# Sheet3.net
KiCad netlist of a schematic drawn in Altium Designer
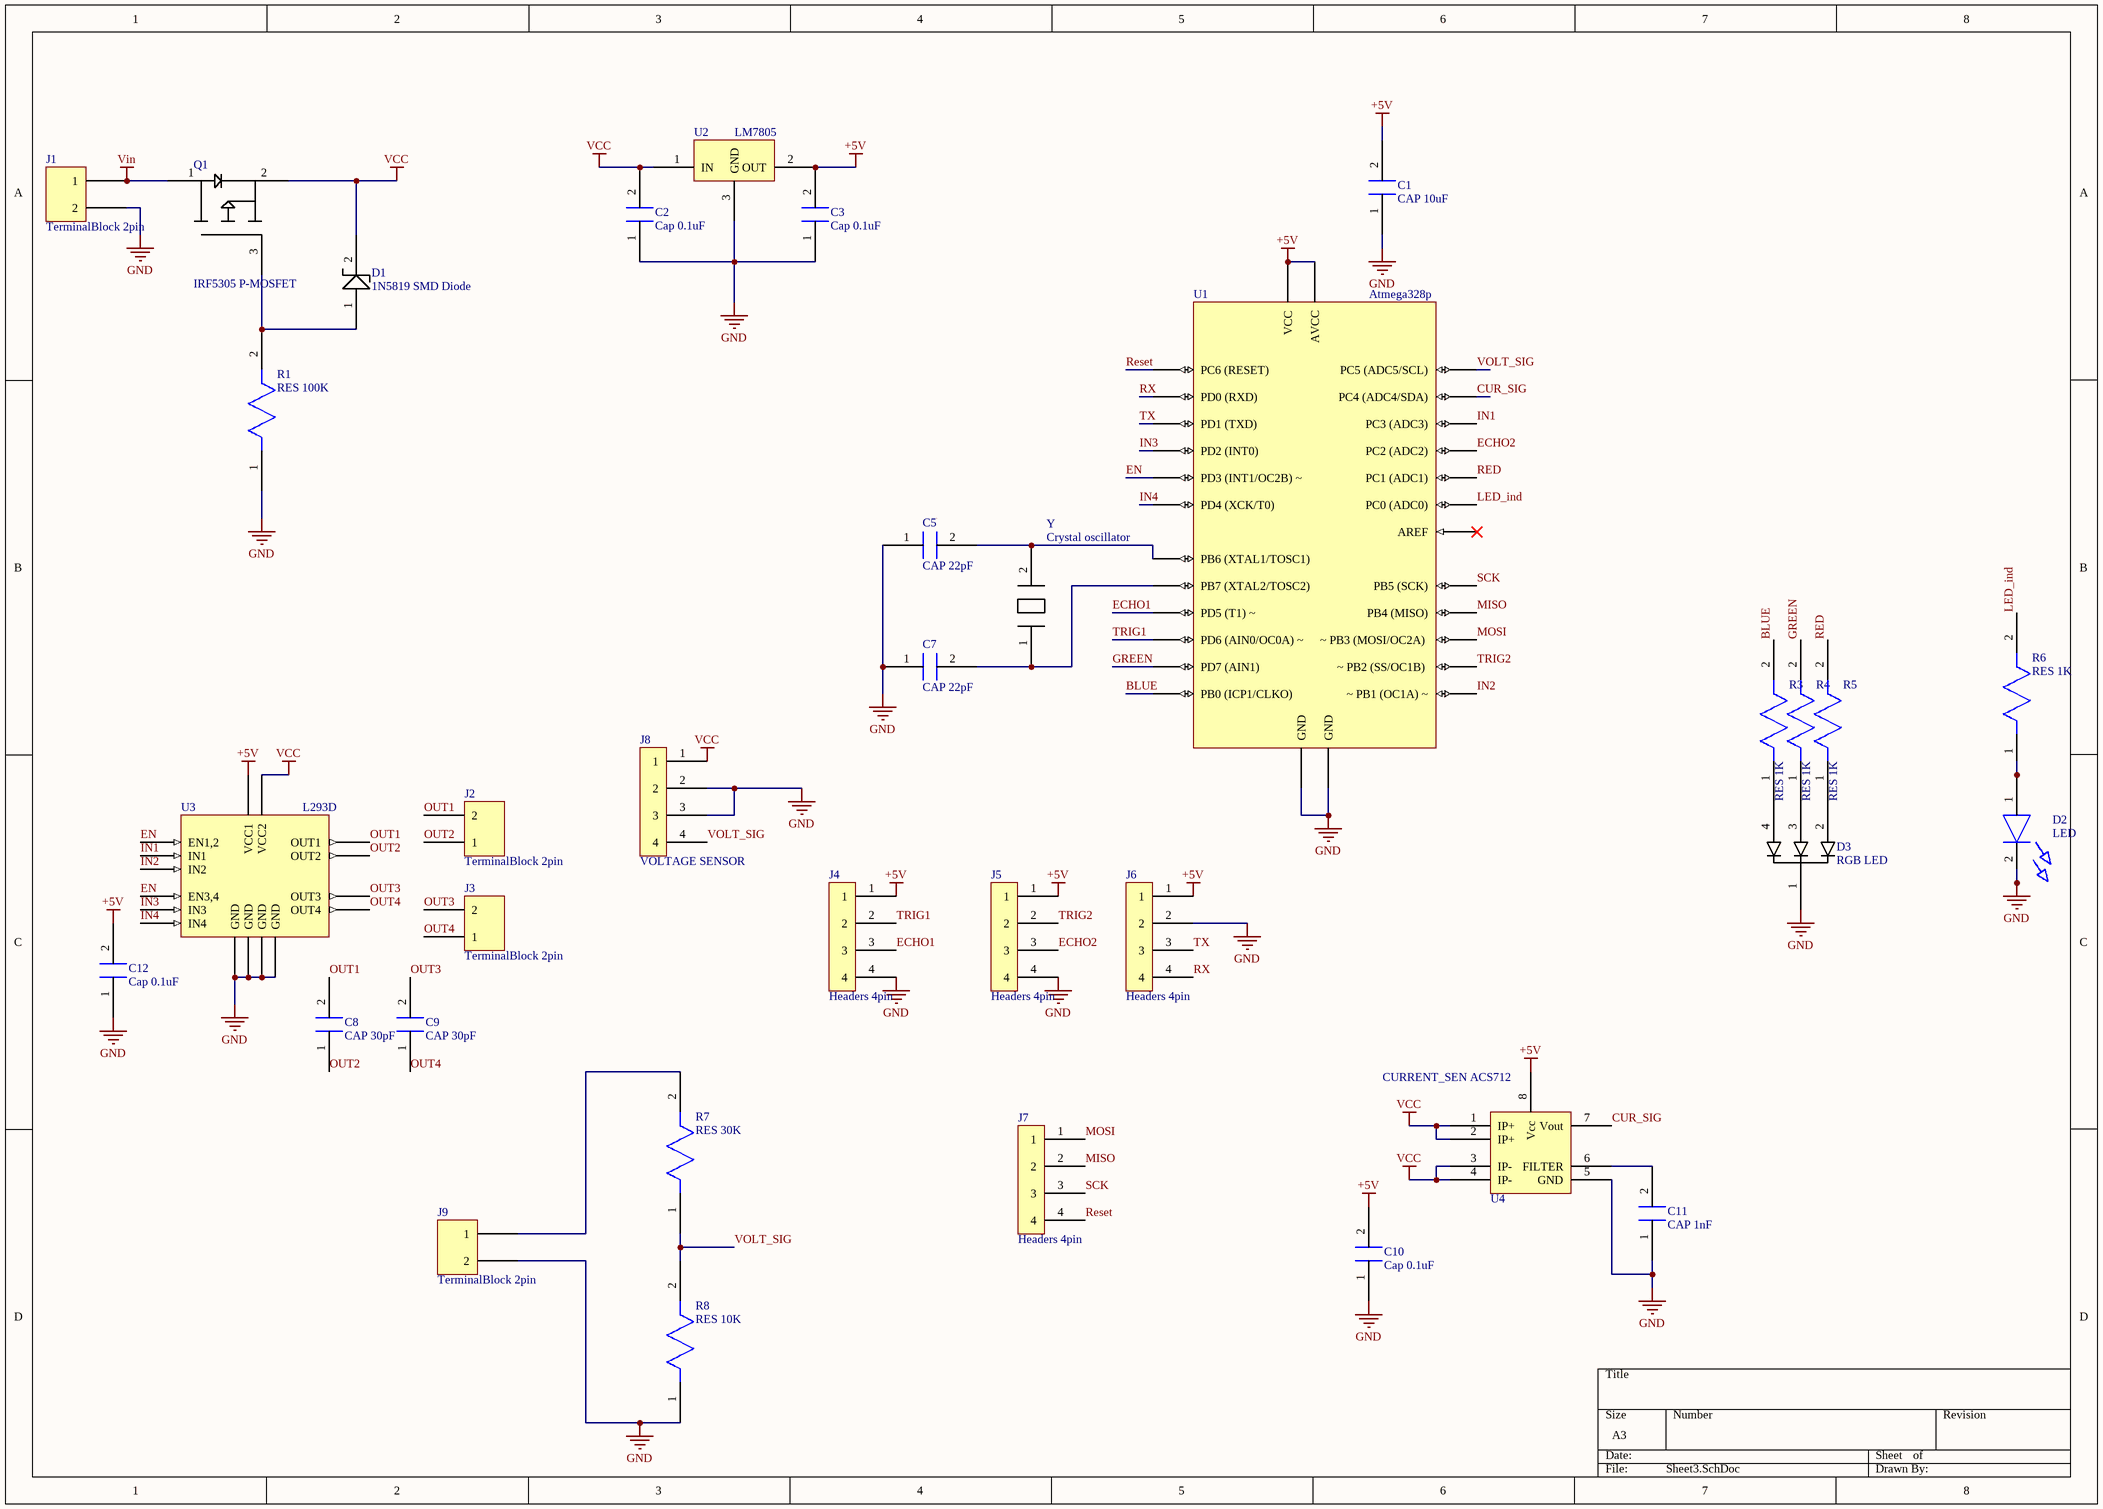
[diagram p0: Sheet3.SchDoc]

(export (version "E")
  (design (tool "Eeschema 10.0.6"))
  (components
    (comp (ref "C1") (value "CAP 10uF") (footprint "Cap 10uF") (libsource (lib "Schlib1") (part "CAP 10uF")))
    (comp (ref "C2")
      (value "Cap 0.1uF")
      (footprint "CAP 0.1uF")
      (libsource (lib "Schlib1") (part "Cap 0.1uF"))
    )
    (comp (ref "C3")
      (value "Cap 0.1uF")
      (footprint "CAP 0.1uF")
      (libsource (lib "Schlib1") (part "Cap 0.1uF"))
    )
    (comp (ref "C5") (value "CAP 22pF") (footprint "Cap 22pF") (libsource (lib "Schlib1") (part "CAP 22pF")))
    (comp (ref "C7") (value "CAP 22pF") (footprint "Cap 22pF") (libsource (lib "Schlib1") (part "CAP 22pF")))
    (comp (ref "C8") (value "CAP 30pF") (footprint "CAP 30pF") (libsource (lib "Schlib1") (part "CAP 30pF")))
    (comp (ref "C9") (value "CAP 30pF") (footprint "CAP 30pF") (libsource (lib "Schlib1") (part "CAP 30pF")))
    (comp (ref "C10")
      (value "Cap 0.1uF")
      (footprint "CAP 0.1uF")
      (libsource (lib "Schlib1") (part "Cap 0.1uF"))
    )
    (comp (ref "C11") (value "CAP 1nF") (footprint "CAP 1nF") (libsource (lib "Schlib1") (part "CAP 1nF")))
    (comp (ref "C12")
      (value "Cap 0.1uF")
      (footprint "CAP 0.1uF")
      (libsource (lib "Schlib1") (part "Cap 0.1uF"))
    )
    (comp (ref "D1")
      (value "1N5819 SMD Diode")
      (footprint "1N5819 SMD Diode")
      (libsource (lib "Schlib1") (part "1N5819 SMD Diode"))
    )
    (comp (ref "D2") (value "LED") (footprint "LED") (libsource (lib "Schlib1") (part "LED")))
    (comp (ref "D3") (value "RGB LED") (footprint "RGB LED") (libsource (lib "Schlib1") (part "RGB LED")))
    (comp (ref "J1")
      (value "TerminalBlock 2pin")
      (footprint "Terminal Block 2pin")
      (libsource (lib "Schlib1") (part "TerminalBlock 2pin"))
    )
    (comp (ref "J2")
      (value "TerminalBlock 2pin")
      (footprint "Terminal Block 2pin")
      (libsource (lib "") (part "TerminalBlock 2pin_1"))
    )
    (comp (ref "J3")
      (value "TerminalBlock 2pin")
      (footprint "Terminal Block 2pin")
      (libsource (lib "") (part "TerminalBlock 2pin_1"))
    )
    (comp (ref "J4")
      (value "Headers 4pin")
      (footprint "Header 4pin")
      (libsource (lib "Schlib1") (part "Headers 4pin"))
    )
    (comp (ref "J5")
      (value "Headers 4pin")
      (footprint "Header 4pin")
      (libsource (lib "Schlib1") (part "Headers 4pin"))
    )
    (comp (ref "J6")
      (value "Headers 4pin")
      (footprint "Header 4pin")
      (libsource (lib "Schlib1") (part "Headers 4pin"))
    )
    (comp (ref "J7")
      (value "Headers 4pin")
      (footprint "Header 4pin")
      (libsource (lib "Schlib1") (part "Headers 4pin"))
    )
    (comp (ref "J8")
      (value "VOLTAGE SENSOR")
      (footprint "Header 4pin")
      (libsource (lib "Schlib1") (part "Headers 4pin"))
    )
    (comp (ref "J9")
      (value "TerminalBlock 2pin")
      (footprint "Terminal Block 2pin")
      (libsource (lib "Schlib1") (part "TerminalBlock 2pin"))
    )
    (comp (ref "Q1")
      (value "IRF5305 P-MOSFET")
      (footprint "IRF5305")
      (libsource (lib "Schlib1") (part "IRF5305 P-MOSFET"))
    )
    (comp (ref "R1") (value "RES 100K") (footprint "Res100K") (libsource (lib "Schlib1") (part "RES 100K")))
    (comp (ref "R3") (value "RES 1K") (footprint "Res 1K") (libsource (lib "Schlib1") (part "RES 1K")))
    (comp (ref "R4") (value "RES 1K") (footprint "Res 1K") (libsource (lib "Schlib1") (part "RES 1K")))
    (comp (ref "R5") (value "RES 1K") (footprint "Res 1K") (libsource (lib "Schlib1") (part "RES 1K")))
    (comp (ref "R6") (value "RES 1K") (footprint "Res 1K") (libsource (lib "Schlib1") (part "RES 1K")))
    (comp (ref "R7") (value "RES 30K") (footprint "Res100K") (libsource (lib "Schlib1") (part "RES 100K")))
    (comp (ref "R8") (value "RES 10K") (footprint "Res10K") (libsource (lib "Schlib1") (part "RES 10K")))
    (comp (ref "U1")
      (value "Atmega328p")
      (footprint "ATMega 328 P-PU - duplicate")
      (libsource (lib "Schlib1") (part "Atmega328p"))
    )
    (comp (ref "U2") (value "LM7805") (footprint "LM7805") (libsource (lib "Schlib1") (part "LM7805")))
    (comp (ref "U3") (value "L293D") (footprint "L293D") (libsource (lib "Schlib1") (part "L293D")))
    (comp (ref "U4")
      (value "CURRENT_SEN ACS712")
      (footprint "Cuurent_sens")
      (libsource (lib "Schlib1") (part "CURRENT_MOD ACS712"))
    )
    (comp (ref "Y")
      (value "Crystal oscillator")
      (footprint "Crrystal 16MHZ")
      (libsource (lib "Schlib1") (part "Crystal oscillator"))
    )
  )
  (nets
    (net (code "1") (name "+5V") (class "Default")
      (node (ref "C1") (pin "2") (pinfunction "2_2") (pintype "passive"))
      (node (ref "C10") (pin "2") (pinfunction "2_2") (pintype "passive"))
      (node (ref "C12") (pin "2") (pinfunction "2_2") (pintype "passive"))
      (node (ref "C3") (pin "2") (pinfunction "2_2") (pintype "passive"))
      (node (ref "J4") (pin "1") (pinfunction "1_1") (pintype "passive"))
      (node (ref "J5") (pin "1") (pinfunction "1_1") (pintype "passive"))
      (node (ref "J6") (pin "1") (pinfunction "1_1") (pintype "passive"))
      (node (ref "U1") (pin "20") (pinfunction "AVCC_20") (pintype "passive"))
      (node (ref "U1") (pin "7") (pinfunction "VCC_7") (pintype "passive"))
      (node (ref "U2") (pin "2") (pinfunction "OUT_2") (pintype "passive"))
      (node (ref "U3") (pin "16") (pinfunction "VCC1_16") (pintype "power_in"))
      (node (ref "U4") (pin "8") (pinfunction "Vcc_8") (pintype "passive"))
    )
    (net (code "3") (name "/BLUE") (class "Default")
      (node (ref "R3") (pin "2") (pinfunction "4_2") (pintype "passive"))
      (node (ref "U1") (pin "14") (pinfunction "PB0_(ICP1/CLKO)_14") (pintype "bidirectional"))
    )
    (net (code "4") (name "/CUR_SIG") (class "Default")
      (node (ref "U1") (pin "27") (pinfunction "PC4_(ADC4/SDA)_27") (pintype "bidirectional"))
      (node (ref "U4") (pin "7") (pinfunction "Vout_7") (pintype "passive"))
    )
    (net (code "5") (name "/ECHO1") (class "Default")
      (node (ref "J4") (pin "3") (pinfunction "3_3") (pintype "passive"))
      (node (ref "U1") (pin "11") (pinfunction "PD5_(T1)_~_11") (pintype "bidirectional"))
    )
    (net (code "6") (name "/ECHO2") (class "Default")
      (node (ref "J5") (pin "3") (pinfunction "3_3") (pintype "passive"))
      (node (ref "U1") (pin "25") (pinfunction "PC2_(ADC2)_25") (pintype "bidirectional"))
    )
    (net (code "7") (name "/EN") (class "Default")
      (node (ref "U1") (pin "5") (pinfunction "PD3_(INT1/OC2B)_~_5") (pintype "bidirectional"))
      (node (ref "U3") (pin "1") (pinfunction "EN1,2_1") (pintype "input"))
      (node (ref "U3") (pin "9") (pinfunction "EN3,4_9") (pintype "input"))
    )
    (net (code "8") (name "/GREEN") (class "Default")
      (node (ref "R4") (pin "2") (pinfunction "4_2") (pintype "passive"))
      (node (ref "U1") (pin "13") (pinfunction "PD7_(AIN1)_13") (pintype "bidirectional"))
    )
    (net (code "9") (name "/IN1") (class "Default")
      (node (ref "U1") (pin "26") (pinfunction "PC3_(ADC3)_26") (pintype "bidirectional"))
      (node (ref "U3") (pin "2") (pinfunction "IN1_2") (pintype "input"))
    )
    (net (code "10") (name "/IN2") (class "Default")
      (node (ref "U1") (pin "15") (pinfunction "~_PB1_(OC1A)_~_15") (pintype "bidirectional"))
      (node (ref "U3") (pin "7") (pinfunction "IN2_7") (pintype "input"))
    )
    (net (code "11") (name "/IN3") (class "Default")
      (node (ref "U1") (pin "4") (pinfunction "PD2_(INT0)_4") (pintype "bidirectional"))
      (node (ref "U3") (pin "10") (pinfunction "IN3_10") (pintype "input"))
    )
    (net (code "12") (name "/IN4") (class "Default")
      (node (ref "U1") (pin "6") (pinfunction "PD4_(XCK/T0)_6") (pintype "bidirectional"))
      (node (ref "U3") (pin "15") (pinfunction "IN4_15") (pintype "input"))
    )
    (net (code "13") (name "/LED_ind") (class "Default")
      (node (ref "R6") (pin "2") (pinfunction "4_2") (pintype "passive"))
      (node (ref "U1") (pin "23") (pinfunction "PC0_(ADC0)_23") (pintype "bidirectional"))
    )
    (net (code "14") (name "/MISO") (class "Default")
      (node (ref "J7") (pin "2") (pinfunction "2_2") (pintype "passive"))
      (node (ref "U1") (pin "18") (pinfunction "PB4_(MISO)_18") (pintype "bidirectional"))
    )
    (net (code "15") (name "/MOSI") (class "Default")
      (node (ref "J7") (pin "1") (pinfunction "1_1") (pintype "passive"))
      (node (ref "U1") (pin "17") (pinfunction "~_PB3_(MOSI/OC2A)_17") (pintype "bidirectional"))
    )
    (net (code "16") (name "/OUT1") (class "Default")
      (node (ref "C8") (pin "2") (pinfunction "2_2") (pintype "passive"))
      (node (ref "J2") (pin "2") (pinfunction "2_2") (pintype "passive"))
      (node (ref "U3") (pin "3") (pinfunction "OUT1_3") (pintype "output"))
    )
    (net (code "17") (name "/OUT2") (class "Default")
      (node (ref "C8") (pin "1") (pinfunction "1_1") (pintype "passive"))
      (node (ref "J2") (pin "1") (pinfunction "1_1") (pintype "passive"))
      (node (ref "U3") (pin "6") (pinfunction "OUT2_6") (pintype "output"))
    )
    (net (code "18") (name "/OUT3") (class "Default")
      (node (ref "C9") (pin "2") (pinfunction "2_2") (pintype "passive"))
      (node (ref "J3") (pin "2") (pinfunction "2_2") (pintype "passive"))
      (node (ref "U3") (pin "11") (pinfunction "OUT3_11") (pintype "output"))
    )
    (net (code "19") (name "/OUT4") (class "Default")
      (node (ref "C9") (pin "1") (pinfunction "1_1") (pintype "passive"))
      (node (ref "J3") (pin "1") (pinfunction "1_1") (pintype "passive"))
      (node (ref "U3") (pin "14") (pinfunction "OUT4_14") (pintype "output"))
    )
    (net (code "20") (name "/RED") (class "Default")
      (node (ref "R5") (pin "2") (pinfunction "4_2") (pintype "passive"))
      (node (ref "U1") (pin "24") (pinfunction "PC1_(ADC1)_24") (pintype "bidirectional"))
    )
    (net (code "21") (name "/RX") (class "Default")
      (node (ref "J6") (pin "4") (pinfunction "4_4") (pintype "passive"))
      (node (ref "U1") (pin "2") (pinfunction "PD0_(RXD)_2") (pintype "bidirectional"))
    )
    (net (code "22") (name "/Reset") (class "Default")
      (node (ref "J7") (pin "4") (pinfunction "4_4") (pintype "passive"))
      (node (ref "U1") (pin "1") (pinfunction "PC6_(RESET)_1") (pintype "bidirectional"))
    )
    (net (code "23") (name "/SCK") (class "Default")
      (node (ref "J7") (pin "3") (pinfunction "3_3") (pintype "passive"))
      (node (ref "U1") (pin "19") (pinfunction "PB5_(SCK)_19") (pintype "bidirectional"))
    )
    (net (code "24") (name "/TRIG1") (class "Default")
      (node (ref "J4") (pin "2") (pinfunction "2_2") (pintype "passive"))
      (node (ref "U1") (pin "12") (pinfunction "PD6_(AIN0/OC0A)_~_12") (pintype "bidirectional"))
    )
    (net (code "25") (name "/TRIG2") (class "Default")
      (node (ref "J5") (pin "2") (pinfunction "2_2") (pintype "passive"))
      (node (ref "U1") (pin "16") (pinfunction "~_PB2_(SS/OC1B)_16") (pintype "bidirectional"))
    )
    (net (code "26") (name "/TX") (class "Default")
      (node (ref "J6") (pin "3") (pinfunction "3_3") (pintype "passive"))
      (node (ref "U1") (pin "3") (pinfunction "PD1_(TXD)_3") (pintype "bidirectional"))
    )
    (net (code "27") (name "/VOLT_SIG") (class "Default")
      (node (ref "J8") (pin "4") (pinfunction "4_4") (pintype "passive"))
      (node (ref "R7") (pin "1") (pinfunction "3_1") (pintype "passive"))
      (node (ref "R8") (pin "2") (pinfunction "4_2") (pintype "passive"))
      (node (ref "U1") (pin "28") (pinfunction "PC5_(ADC5/SCL)_28") (pintype "bidirectional"))
    )
    (net (code "28") (name "GND") (class "Default")
      (node (ref "C1") (pin "1") (pinfunction "1_1") (pintype "passive"))
      (node (ref "C10") (pin "1") (pinfunction "1_1") (pintype "passive"))
      (node (ref "C11") (pin "1") (pinfunction "1_1") (pintype "passive"))
      (node (ref "C12") (pin "1") (pinfunction "1_1") (pintype "passive"))
      (node (ref "C2") (pin "1") (pinfunction "1_1") (pintype "passive"))
      (node (ref "C3") (pin "1") (pinfunction "1_1") (pintype "passive"))
      (node (ref "C5") (pin "1") (pinfunction "1_1") (pintype "passive"))
      (node (ref "C7") (pin "1") (pinfunction "1_1") (pintype "passive"))
      (node (ref "D2") (pin "2") (pinfunction "6_2") (pintype "passive"))
      (node (ref "D3") (pin "1") (pinfunction "(-)_1") (pintype "passive"))
      (node (ref "J1") (pin "2") (pinfunction "2_2") (pintype "passive"))
      (node (ref "J4") (pin "4") (pinfunction "4_4") (pintype "passive"))
      (node (ref "J5") (pin "4") (pinfunction "4_4") (pintype "passive"))
      (node (ref "J6") (pin "2") (pinfunction "2_2") (pintype "passive"))
      (node (ref "J8") (pin "2") (pinfunction "2_2") (pintype "passive"))
      (node (ref "J8") (pin "3") (pinfunction "3_3") (pintype "passive"))
      (node (ref "J9") (pin "2") (pinfunction "2_2") (pintype "passive"))
      (node (ref "R1") (pin "1") (pinfunction "3_1") (pintype "passive"))
      (node (ref "R8") (pin "1") (pinfunction "3_1") (pintype "passive"))
      (node (ref "U1") (pin "22") (pinfunction "GND_22") (pintype "passive"))
      (node (ref "U1") (pin "8") (pinfunction "GND_8") (pintype "passive"))
      (node (ref "U2") (pin "3") (pinfunction "GND_3") (pintype "power_in"))
      (node (ref "U3") (pin "12") (pinfunction "GND_12") (pintype "power_in"))
      (node (ref "U3") (pin "13") (pinfunction "GND_13") (pintype "power_in"))
      (node (ref "U3") (pin "4") (pinfunction "GND_4") (pintype "power_in"))
      (node (ref "U3") (pin "5") (pinfunction "GND_5") (pintype "power_in"))
      (node (ref "U4") (pin "5") (pinfunction "GND_5") (pintype "passive"))
    )
    (net (code "29") (name "Net-(D1-200)") (class "Default")
      (node (ref "D1") (pin "1") (pinfunction "200_1") (pintype "passive"))
      (node (ref "Q1") (pin "3") (pinfunction "G_3") (pintype "passive"))
      (node (ref "R1") (pin "2") (pinfunction "4_2") (pintype "passive"))
    )
    (net (code "30") (name "Net-(D2-7)") (class "Default")
      (node (ref "D2") (pin "1") (pinfunction "7_1") (pintype "passive"))
      (node (ref "R6") (pin "1") (pinfunction "3_1") (pintype "passive"))
    )
    (net (code "31") (name "Net-(D3-B)") (class "Default")
      (node (ref "D3") (pin "4") (pinfunction "B_4") (pintype "passive"))
      (node (ref "R3") (pin "1") (pinfunction "3_1") (pintype "passive"))
    )
    (net (code "32") (name "Net-(D3-G)") (class "Default")
      (node (ref "D3") (pin "3") (pinfunction "G_3") (pintype "passive"))
      (node (ref "R4") (pin "1") (pinfunction "3_1") (pintype "passive"))
    )
    (net (code "33") (name "Net-(D3-R)") (class "Default")
      (node (ref "D3") (pin "2") (pinfunction "R_2") (pintype "passive"))
      (node (ref "R5") (pin "1") (pinfunction "3_1") (pintype "passive"))
    )
    (net (code "34") (name "Net-(R7-4)") (class "Default")
      (node (ref "J9") (pin "1") (pinfunction "1_1") (pintype "passive"))
      (node (ref "R7") (pin "2") (pinfunction "4_2") (pintype "passive"))
    )
    (net (code "35") (name "Net-(U1-PB6_(XTAL1{slash}TOSC1))") (class "Default")
      (node (ref "C5") (pin "2") (pinfunction "2_2") (pintype "passive"))
      (node (ref "U1") (pin "9") (pinfunction "PB6_(XTAL1/TOSC1)_9") (pintype "bidirectional"))
      (node (ref "Y") (pin "2") (pinfunction "2_2") (pintype "passive"))
    )
    (net (code "36") (name "Net-(U1-PB7_(XTAL2{slash}TOSC2))") (class "Default")
      (node (ref "C7") (pin "2") (pinfunction "2_2") (pintype "passive"))
      (node (ref "U1") (pin "10") (pinfunction "PB7_(XTAL2/TOSC2)_10") (pintype "bidirectional"))
      (node (ref "Y") (pin "1") (pinfunction "1_1") (pintype "passive"))
    )
    (net (code "37") (name "Net-(U4-FILTER)") (class "Default")
      (node (ref "C11") (pin "2") (pinfunction "2_2") (pintype "passive"))
      (node (ref "U4") (pin "6") (pinfunction "FILTER_6") (pintype "passive"))
    )
    (net (code "38") (name "VCC") (class "Default")
      (node (ref "C2") (pin "2") (pinfunction "2_2") (pintype "passive"))
      (node (ref "D1") (pin "2") (pinfunction "100_2") (pintype "passive"))
      (node (ref "J8") (pin "1") (pinfunction "1_1") (pintype "passive"))
      (node (ref "Q1") (pin "2") (pinfunction "S_2") (pintype "passive"))
      (node (ref "U2") (pin "1") (pinfunction "IN_1") (pintype "passive"))
      (node (ref "U3") (pin "8") (pinfunction "VCC2_8") (pintype "power_in"))
      (node (ref "U4") (pin "1") (pinfunction "IP+_1") (pintype "passive"))
      (node (ref "U4") (pin "2") (pinfunction "IP+_2") (pintype "passive"))
      (node (ref "U4") (pin "3") (pinfunction "IP-_3") (pintype "passive"))
      (node (ref "U4") (pin "4") (pinfunction "IP-_4") (pintype "passive"))
    )
    (net (code "39") (name "Vin") (class "Default")
      (node (ref "J1") (pin "1") (pinfunction "1_1") (pintype "passive"))
      (node (ref "Q1") (pin "1") (pinfunction "D_1") (pintype "passive"))
    )
    (net (code "40") (name "unconnected-(U1-AREF-Pad21)") (class "Default")
      (node (ref "U1") (pin "21") (pinfunction "AREF_21") (pintype "input+no_connect"))
    )
  )
)
